# SPL06.net
KiCad netlist of a schematic drawn in Altium Designer
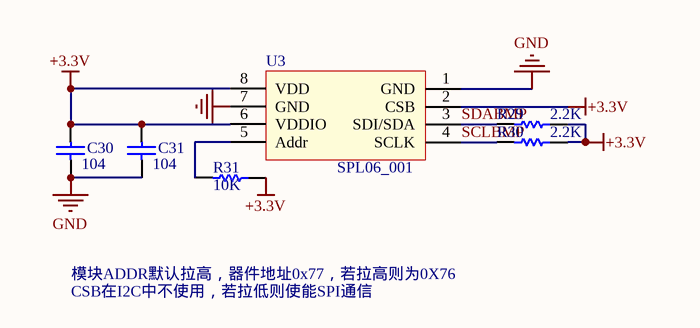
[diagram p0: SPL06.SchDoc]

(export (version "E")
  (design (tool "Eeschema 10.0.6"))
  (components
    (comp (ref "C30")
      (value "104")
      (footprint "0603_C")
      (description "Cap_0603")
      (fields (field (name "PUBLISHER") "Altium Limited"))
      (libsource (lib "ChapuIntegratedLibrary") (part "Cap Chip 1206"))
    )
    (comp (ref "C31")
      (value "104")
      (footprint "0603_C")
      (description "Cap_0603")
      (fields (field (name "PUBLISHER") "Altium Limited"))
      (libsource (lib "ChapuIntegratedLibrary") (part "Cap Chip 1206"))
    )
    (comp (ref "R29")
      (value "2.2K")
      (footprint "0603R")
      (description "Resistor-0603")
      (fields (field (name "PUBLISHER") "Altium Limited"))
      (libsource (lib "Miscellaneous Devices") (part "Res1"))
    )
    (comp (ref "R30")
      (value "2.2K")
      (footprint "0603R")
      (description "Resistor-0603")
      (fields (field (name "PUBLISHER") "Altium Limited"))
      (libsource (lib "Miscellaneous Devices") (part "Res1"))
    )
    (comp (ref "R31")
      (value "10K")
      (footprint "0603R")
      (description "Resistor-0603")
      (fields (field (name "PUBLISHER") "Altium Limited"))
      (libsource (lib "Miscellaneous Devices") (part "Res1"))
    )
    (comp (ref "U3") (value "SPL06_001") (footprint "FBM320") (libsource (lib "quadrotor") (part "FBM320")))
  )
  (nets
    (net (code "1") (name "+3.3V") (class "Default")
      (node (ref "C30") (pin "2") (pinfunction "2_2") (pintype "passive"))
      (node (ref "C31") (pin "2") (pinfunction "2_2") (pintype "passive"))
      (node (ref "R29") (pin "1") (pinfunction "1_1") (pintype "passive"))
      (node (ref "R30") (pin "1") (pinfunction "1_1") (pintype "passive"))
      (node (ref "R31") (pin "1") (pinfunction "1_1") (pintype "passive"))
      (node (ref "U3") (pin "2") (pinfunction "CSB_2") (pintype "passive"))
      (node (ref "U3") (pin "6") (pinfunction "VDDIO_6") (pintype "passive"))
      (node (ref "U3") (pin "8") (pinfunction "VDD_8") (pintype "passive"))
    )
    (net (code "2") (name "/SCLBMP") (class "Default")
      (node (ref "R30") (pin "2") (pinfunction "2_2") (pintype "passive"))
      (node (ref "U3") (pin "4") (pinfunction "SCLK_4") (pintype "passive"))
    )
    (net (code "3") (name "/SDABMP") (class "Default")
      (node (ref "R29") (pin "2") (pinfunction "2_2") (pintype "passive"))
      (node (ref "U3") (pin "3") (pinfunction "SDI/SDA_3") (pintype "passive"))
    )
    (net (code "4") (name "GND") (class "Default")
      (node (ref "C30") (pin "1") (pinfunction "1_1") (pintype "passive"))
      (node (ref "C31") (pin "1") (pinfunction "1_1") (pintype "passive"))
      (node (ref "U3") (pin "1") (pinfunction "GND_1") (pintype "passive"))
      (node (ref "U3") (pin "7") (pinfunction "GND_7") (pintype "passive"))
    )
    (net (code "5") (name "Net-(U3-Addr)") (class "Default")
      (node (ref "R31") (pin "2") (pinfunction "2_2") (pintype "passive"))
      (node (ref "U3") (pin "5") (pinfunction "Addr_5") (pintype "passive"))
    )
  )
)
